# PCM2706_Bus_Powered_USB_DAC_2.net
KiCad netlist of a schematic drawn in Altium Designer
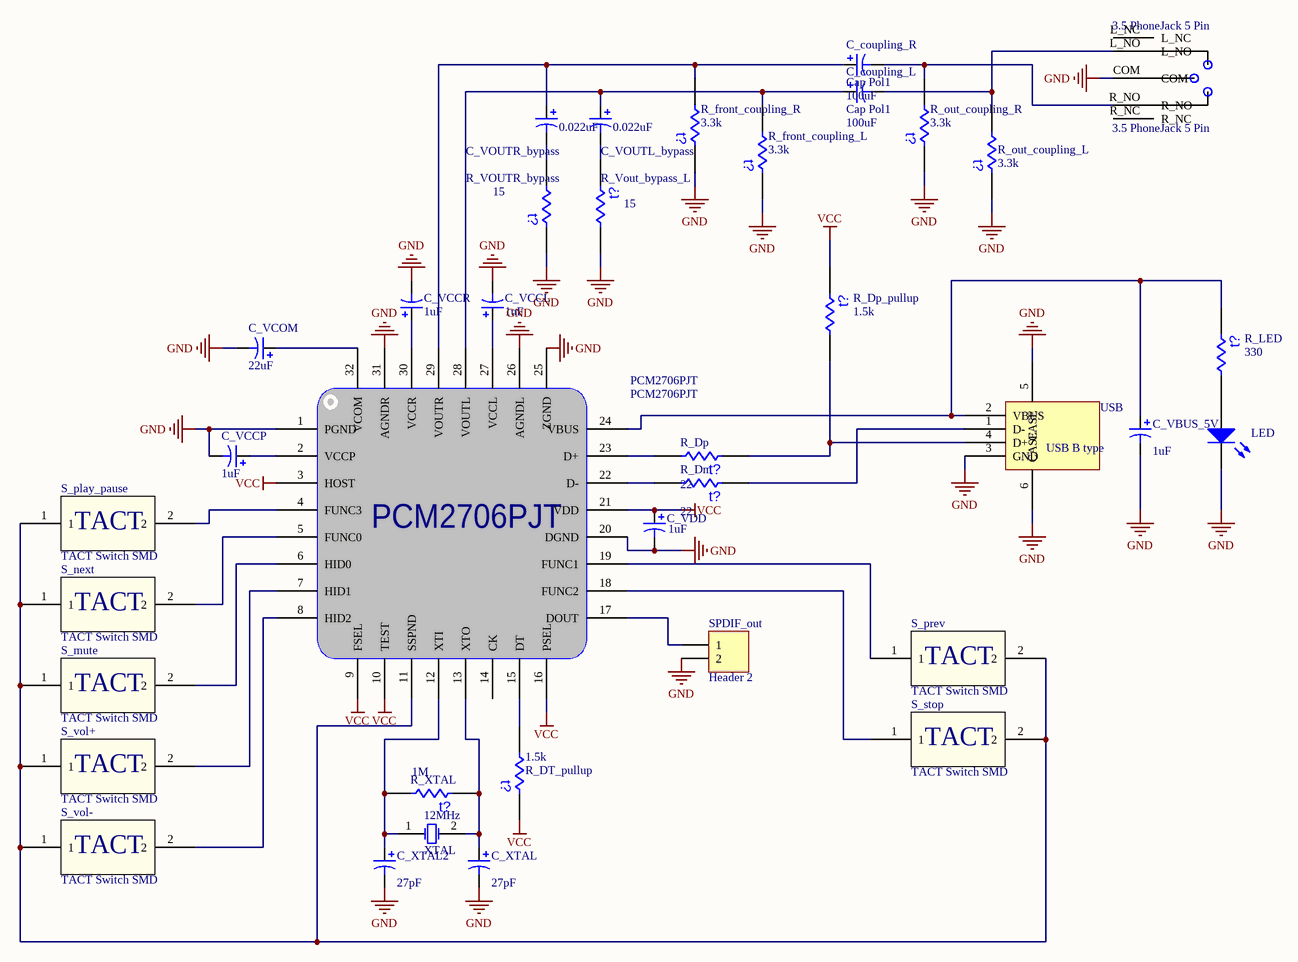
[diagram p0: PCM2706 Bus Powered USB DAC 2.SchDoc]

(export (version "E")
  (design (tool "Eeschema 10.0.6"))
  (components
    (comp (ref "1.5k")
      (value "R_DT_pullup")
      (footprint "6-0805_N")
      (description "Thermistor")
      (fields (field (name "PUBLISHER") "Altium Limited"))
      (libsource (lib "Miscellaneous Devices") (part "Res Thermal"))
    )
    (comp (ref "3.5 PhoneJack 5 Pin")
      (value "3.5 PhoneJack 5 Pin")
      (footprint "3.5 PhoneJack 5 Pin")
      (libsource (lib "misc") (part "3.5 PhoneJack 5 Pin"))
    )
    (comp (ref "12MHz")
      (value "XTAL")
      (footprint "12MHz Crystal OSC through hole")
      (description "Crystal Oscillator")
      (fields (field (name "PUBLISHER") "Altium Limited"))
      (libsource (lib "Miscellaneous Devices") (part "XTAL"))
    )
    (comp (ref "C_coupling_L")
      (value "Cap Pol1")
      (footprint "RB5-10.5_narrowed")
      (description "Polarized Capacitor (Radial)")
      (fields (field (name "ALTIUM_VALUE") "100uF") (field (name "PUBLISHER") "Altium Limited"))
      (libsource (lib "Miscellaneous Devices") (part "Cap Pol1"))
    )
    (comp (ref "C_coupling_R")
      (value "Cap Pol1")
      (footprint "RB5-10.5_narrowed")
      (description "Polarized Capacitor (Radial)")
      (fields (field (name "ALTIUM_VALUE") "100uF") (field (name "PUBLISHER") "Altium Limited"))
      (libsource (lib "Miscellaneous Devices") (part "Cap Pol1"))
    )
    (comp (ref "C_VBUS_5V")
      (value "1uF")
      (footprint "C0805")
      (description "Polarized Capacitor (Surface Mount)")
      (fields (field (name "PUBLISHER") "Altium Limited"))
      (libsource (lib "Miscellaneous Devices") (part "Cap Pol3"))
    )
    (comp (ref "C_VCCL")
      (value "1uF")
      (footprint "C0805")
      (description "Polarized Capacitor (Surface Mount)")
      (fields (field (name "PUBLISHER") "Altium Limited"))
      (libsource (lib "Miscellaneous Devices") (part "Cap Pol3"))
    )
    (comp (ref "C_VCCP")
      (value "1uF")
      (footprint "C0805")
      (description "Polarized Capacitor (Surface Mount)")
      (fields (field (name "PUBLISHER") "Altium Limited"))
      (libsource (lib "Miscellaneous Devices") (part "Cap Pol3"))
    )
    (comp (ref "C_VCCR")
      (value "1uF")
      (footprint "C0805")
      (description "Polarized Capacitor (Surface Mount)")
      (fields (field (name "PUBLISHER") "Altium Limited"))
      (libsource (lib "Miscellaneous Devices") (part "Cap Pol3"))
    )
    (comp (ref "C_VCOM")
      (value "22uF")
      (footprint "Tantalum 6032-28 case C kemet")
      (description "Polarized Capacitor (Surface Mount)")
      (fields (field (name "PUBLISHER") "Altium Limited"))
      (libsource (lib "Miscellaneous Devices") (part "Cap Pol3"))
    )
    (comp (ref "C_VDD")
      (value "1uF")
      (footprint "C0805")
      (description "Polarized Capacitor (Surface Mount)")
      (fields (field (name "PUBLISHER") "Altium Limited"))
      (libsource (lib "Miscellaneous Devices") (part "Cap Pol3"))
    )
    (comp (ref "C_VOUTL_bypass")
      (value "0.022uF")
      (footprint "C0805")
      (description "Polarized Capacitor (Surface Mount)")
      (fields (field (name "PUBLISHER") "Altium Limited"))
      (libsource (lib "Miscellaneous Devices") (part "Cap Pol3"))
    )
    (comp (ref "C_VOUTR_bypass")
      (value "0.022uF")
      (footprint "C0805")
      (description "Polarized Capacitor (Surface Mount)")
      (fields (field (name "PUBLISHER") "Altium Limited"))
      (libsource (lib "Miscellaneous Devices") (part "Cap Pol3"))
    )
    (comp (ref "C_XTAL")
      (value "27pF")
      (footprint "C0805")
      (description "Polarized Capacitor (Surface Mount)")
      (fields (field (name "PUBLISHER") "Altium Limited"))
      (libsource (lib "Miscellaneous Devices") (part "Cap Pol3"))
    )
    (comp (ref "C_XTAL2")
      (value "27pF")
      (footprint "C0805")
      (description "Polarized Capacitor (Surface Mount)")
      (fields (field (name "PUBLISHER") "Altium Limited"))
      (libsource (lib "Miscellaneous Devices") (part "Cap Pol3"))
    )
    (comp (ref "LED")
      (value "~")
      (footprint "6-0805_N_enlarge")
      (description "Typical RED, GREEN, YELLOW, AMBER GaAs LED")
      (fields (field (name "PUBLISHER") "Altium Limited"))
      (libsource (lib "Miscellaneous Devices") (part "LED2"))
    )
    (comp (ref "PCM2706PJT")
      (value "PCM2706PJT")
      (footprint "PCM2706PJT_2")
      (libsource (lib "misc") (part "PCM2706PJT"))
    )
    (comp (ref "R_Dm")
      (value "22")
      (footprint "6-0805_N")
      (description "Thermistor")
      (fields (field (name "PUBLISHER") "Altium Limited"))
      (libsource (lib "Miscellaneous Devices") (part "Res Thermal"))
    )
    (comp (ref "R_Dp")
      (value "22")
      (footprint "6-0805_N")
      (description "Thermistor")
      (fields (field (name "PUBLISHER") "Altium Limited"))
      (libsource (lib "Miscellaneous Devices") (part "Res Thermal"))
    )
    (comp (ref "R_Dp_pullup")
      (value "1.5k")
      (footprint "6-0805_N")
      (description "Thermistor")
      (fields (field (name "PUBLISHER") "Altium Limited"))
      (libsource (lib "Miscellaneous Devices") (part "Res Thermal"))
    )
    (comp (ref "R_front_coupling_L")
      (value "3.3k")
      (footprint "6-0805_N")
      (description "Thermistor")
      (fields (field (name "PUBLISHER") "Altium Limited"))
      (libsource (lib "Miscellaneous Devices") (part "Res Thermal"))
    )
    (comp (ref "R_front_coupling_R")
      (value "3.3k")
      (footprint "6-0805_N")
      (description "Thermistor")
      (fields (field (name "PUBLISHER") "Altium Limited"))
      (libsource (lib "Miscellaneous Devices") (part "Res Thermal"))
    )
    (comp (ref "R_LED")
      (value "330")
      (footprint "6-0805_N")
      (description "Thermistor")
      (fields (field (name "PUBLISHER") "Altium Limited"))
      (libsource (lib "Miscellaneous Devices") (part "Res Thermal"))
    )
    (comp (ref "R_out_coupling_L")
      (value "3.3k")
      (footprint "6-0805_N")
      (description "Thermistor")
      (fields (field (name "PUBLISHER") "Altium Limited"))
      (libsource (lib "Miscellaneous Devices") (part "Res Thermal"))
    )
    (comp (ref "R_out_coupling_R")
      (value "3.3k")
      (footprint "6-0805_N")
      (description "Thermistor")
      (fields (field (name "PUBLISHER") "Altium Limited"))
      (libsource (lib "Miscellaneous Devices") (part "Res Thermal"))
    )
    (comp (ref "R_VOUTR_bypass")
      (value "15")
      (footprint "6-0805_N")
      (description "Thermistor")
      (fields (field (name "PUBLISHER") "Altium Limited"))
      (libsource (lib "Miscellaneous Devices") (part "Res Thermal"))
    )
    (comp (ref "R_Vout_bypass_L")
      (value "15")
      (footprint "6-0805_N")
      (description "Thermistor")
      (fields (field (name "PUBLISHER") "Altium Limited"))
      (libsource (lib "Miscellaneous Devices") (part "Res Thermal"))
    )
    (comp (ref "R_XTAL")
      (value "1M")
      (footprint "6-0805_N")
      (description "Thermistor")
      (fields (field (name "PUBLISHER") "Altium Limited"))
      (libsource (lib "Miscellaneous Devices") (part "Res Thermal"))
    )
    (comp (ref "SPDIF_out")
      (value "Header 2")
      (footprint "HDR1X2")
      (description "Header, 2-Pin")
      (fields (field (name "PUBLISHER") "Altium Limited"))
      (libsource (lib "Miscellaneous Connectors") (part "Header 2"))
    )
    (comp (ref "S_mute")
      (value "TACT Switch SMD")
      (footprint "TACT Switch SMD")
      (libsource (lib "misc") (part "TACT Switch SMD"))
    )
    (comp (ref "S_next")
      (value "TACT Switch SMD")
      (footprint "TACT Switch SMD")
      (libsource (lib "misc") (part "TACT Switch SMD"))
    )
    (comp (ref "S_play_pause")
      (value "TACT Switch SMD")
      (footprint "TACT Switch SMD")
      (libsource (lib "misc") (part "TACT Switch SMD"))
    )
    (comp (ref "S_prev")
      (value "TACT Switch SMD")
      (footprint "TACT Switch SMD")
      (libsource (lib "misc") (part "TACT Switch SMD"))
    )
    (comp (ref "S_stop")
      (value "TACT Switch SMD")
      (footprint "TACT Switch SMD")
      (libsource (lib "misc") (part "TACT Switch SMD"))
    )
    (comp (ref "S_vol+")
      (value "TACT Switch SMD")
      (footprint "TACT Switch SMD")
      (libsource (lib "misc") (part "TACT Switch SMD"))
    )
    (comp (ref "S_vol-")
      (value "TACT Switch SMD")
      (footprint "TACT Switch SMD")
      (libsource (lib "misc") (part "TACT Switch SMD"))
    )
    (comp (ref "USB")
      (value "USB B type")
      (footprint "USB2.5-2H4D")
      (libsource (lib "misc") (part "USB B type"))
    )
  )
  (nets
    (net (code "1") (name "GND") (class "Default")
      (node (ref "3.5 PhoneJack 5 Pin") (pin "COM") (pinfunction "COM_COM") (pintype "passive"))
      (node (ref "C_VBUS_5V") (pin "2") (pinfunction "2_2") (pintype "passive"))
      (node (ref "C_VCCL") (pin "2") (pinfunction "2_2") (pintype "passive"))
      (node (ref "C_VCCP") (pin "2") (pinfunction "2_2") (pintype "passive"))
      (node (ref "C_VCCR") (pin "2") (pinfunction "2_2") (pintype "passive"))
      (node (ref "C_VCOM") (pin "2") (pinfunction "2_2") (pintype "passive"))
      (node (ref "C_VDD") (pin "2") (pinfunction "2_2") (pintype "passive"))
      (node (ref "C_XTAL") (pin "2") (pinfunction "2_2") (pintype "passive"))
      (node (ref "C_XTAL2") (pin "2") (pinfunction "2_2") (pintype "passive"))
      (node (ref "LED") (pin "2") (pinfunction "K_2") (pintype "passive"))
      (node (ref "PCM2706PJT") (pin "1") (pinfunction "PGND_1") (pintype "passive"))
      (node (ref "PCM2706PJT") (pin "20") (pinfunction "DGND_20") (pintype "passive"))
      (node (ref "PCM2706PJT") (pin "25") (pinfunction "ZGND_25") (pintype "passive"))
      (node (ref "PCM2706PJT") (pin "26") (pinfunction "AGNDL_26") (pintype "passive"))
      (node (ref "PCM2706PJT") (pin "31") (pinfunction "AGNDR_31") (pintype "passive"))
      (node (ref "R_VOUTR_bypass") (pin "1") (pinfunction "1_1") (pintype "passive"))
      (node (ref "R_Vout_bypass_L") (pin "2") (pinfunction "2_2") (pintype "passive"))
      (node (ref "R_front_coupling_L") (pin "1") (pinfunction "1_1") (pintype "passive"))
      (node (ref "R_front_coupling_R") (pin "1") (pinfunction "1_1") (pintype "passive"))
      (node (ref "R_out_coupling_L") (pin "1") (pinfunction "1_1") (pintype "passive"))
      (node (ref "R_out_coupling_R") (pin "1") (pinfunction "1_1") (pintype "passive"))
      (node (ref "SPDIF_out") (pin "1") (pinfunction "2_1") (pintype "passive"))
      (node (ref "USB") (pin "3") (pinfunction "GND_3") (pintype "passive"))
      (node (ref "USB") (pin "5") (pinfunction "CASE_5") (pintype "passive"))
      (node (ref "USB") (pin "6") (pinfunction "CASE_6") (pintype "passive"))
    )
    (net (code "2") (name "Net-(3.5 PhoneJack 5 Pin-PadL_NO)") (class "Default")
      (node (ref "3.5 PhoneJack 5 Pin") (pin "L_NO") (pinfunction "L_NO_L_NO") (pintype "passive"))
      (node (ref "C_coupling_L") (pin "2") (pinfunction "2_2") (pintype "passive"))
      (node (ref "R_out_coupling_L") (pin "2") (pinfunction "2_2") (pintype "passive"))
    )
    (net (code "3") (name "Net-(3.5 PhoneJack 5 Pin-PadR_NO)") (class "Default")
      (node (ref "3.5 PhoneJack 5 Pin") (pin "R_NO") (pinfunction "R_NO_R_NO") (pintype "passive"))
      (node (ref "C_coupling_R") (pin "2") (pinfunction "2_2") (pintype "passive"))
      (node (ref "R_out_coupling_R") (pin "2") (pinfunction "2_2") (pintype "passive"))
    )
    (net (code "4") (name "Net-(12MHz-OSC1)") (class "Default")
      (node (ref "12MHz") (pin "1") (pinfunction "OSC1_1") (pintype "passive"))
      (node (ref "C_XTAL2") (pin "1") (pinfunction "1_1") (pintype "passive"))
      (node (ref "PCM2706PJT") (pin "12") (pinfunction "XTI_12") (pintype "passive"))
      (node (ref "R_XTAL") (pin "2") (pinfunction "2_2") (pintype "passive"))
    )
    (net (code "5") (name "Net-(12MHz-OSC2)") (class "Default")
      (node (ref "12MHz") (pin "2") (pinfunction "OSC2_2") (pintype "passive"))
      (node (ref "C_XTAL") (pin "1") (pinfunction "1_1") (pintype "passive"))
      (node (ref "PCM2706PJT") (pin "13") (pinfunction "XTO_13") (pintype "passive"))
      (node (ref "R_XTAL") (pin "1") (pinfunction "1_1") (pintype "passive"))
    )
    (net (code "6") (name "Net-(C_VOUTL_bypass-Pad2)") (class "Default")
      (node (ref "C_VOUTL_bypass") (pin "2") (pinfunction "2_2") (pintype "passive"))
      (node (ref "R_Vout_bypass_L") (pin "1") (pinfunction "1_1") (pintype "passive"))
    )
    (net (code "7") (name "Net-(C_VOUTR_bypass-Pad2)") (class "Default")
      (node (ref "C_VOUTR_bypass") (pin "2") (pinfunction "2_2") (pintype "passive"))
      (node (ref "R_VOUTR_bypass") (pin "2") (pinfunction "2_2") (pintype "passive"))
    )
    (net (code "8") (name "Net-(LED-A)") (class "Default")
      (node (ref "LED") (pin "1") (pinfunction "A_1") (pintype "passive"))
      (node (ref "R_LED") (pin "2") (pinfunction "2_2") (pintype "passive"))
    )
    (net (code "9") (name "Net-(PCM2706PJT-D+)") (class "Default")
      (node (ref "PCM2706PJT") (pin "23") (pinfunction "D+_23") (pintype "passive"))
      (node (ref "R_Dp") (pin "2") (pinfunction "2_2") (pintype "passive"))
    )
    (net (code "10") (name "Net-(PCM2706PJT-D-)") (class "Default")
      (node (ref "PCM2706PJT") (pin "22") (pinfunction "D-_22") (pintype "passive"))
      (node (ref "R_Dm") (pin "2") (pinfunction "2_2") (pintype "passive"))
    )
    (net (code "11") (name "Net-(PCM2706PJT-DOUT)") (class "Default")
      (node (ref "PCM2706PJT") (pin "17") (pinfunction "DOUT_17") (pintype "passive"))
      (node (ref "SPDIF_out") (pin "2") (pinfunction "1_2") (pintype "passive"))
    )
    (net (code "12") (name "Net-(PCM2706PJT-DT)") (class "Default")
      (node (ref "1.5k") (pin "2") (pinfunction "2_2") (pintype "passive"))
      (node (ref "PCM2706PJT") (pin "15") (pinfunction "DT_15") (pintype "passive"))
    )
    (net (code "13") (name "Net-(PCM2706PJT-FUNC0)") (class "Default")
      (node (ref "PCM2706PJT") (pin "5") (pinfunction "FUNC0_5") (pintype "passive"))
      (node (ref "S_next") (pin "2") (pinfunction "2_2") (pintype "passive"))
    )
    (net (code "14") (name "Net-(PCM2706PJT-FUNC1)") (class "Default")
      (node (ref "PCM2706PJT") (pin "19") (pinfunction "FUNC1_19") (pintype "passive"))
      (node (ref "S_prev") (pin "1") (pinfunction "1_1") (pintype "passive"))
    )
    (net (code "15") (name "Net-(PCM2706PJT-FUNC2)") (class "Default")
      (node (ref "PCM2706PJT") (pin "18") (pinfunction "FUNC2_18") (pintype "passive"))
      (node (ref "S_stop") (pin "1") (pinfunction "1_1") (pintype "passive"))
    )
    (net (code "16") (name "Net-(PCM2706PJT-FUNC3)") (class "Default")
      (node (ref "PCM2706PJT") (pin "4") (pinfunction "FUNC3_4") (pintype "passive"))
      (node (ref "S_play_pause") (pin "2") (pinfunction "2_2") (pintype "passive"))
    )
    (net (code "17") (name "Net-(PCM2706PJT-HID0)") (class "Default")
      (node (ref "PCM2706PJT") (pin "6") (pinfunction "HID0_6") (pintype "passive"))
      (node (ref "S_mute") (pin "2") (pinfunction "2_2") (pintype "passive"))
    )
    (net (code "18") (name "Net-(PCM2706PJT-HID1)") (class "Default")
      (node (ref "PCM2706PJT") (pin "7") (pinfunction "HID1_7") (pintype "passive"))
      (node (ref "S_vol+") (pin "2") (pinfunction "2_2") (pintype "passive"))
    )
    (net (code "19") (name "Net-(PCM2706PJT-HID2)") (class "Default")
      (node (ref "PCM2706PJT") (pin "8") (pinfunction "HID2_8") (pintype "passive"))
      (node (ref "S_vol-") (pin "2") (pinfunction "2_2") (pintype "passive"))
    )
    (net (code "20") (name "Net-(PCM2706PJT-SSPND)") (class "Default")
      (node (ref "PCM2706PJT") (pin "11") (pinfunction "SSPND_11") (pintype "passive"))
      (node (ref "S_mute") (pin "1") (pinfunction "1_1") (pintype "passive"))
      (node (ref "S_next") (pin "1") (pinfunction "1_1") (pintype "passive"))
      (node (ref "S_play_pause") (pin "1") (pinfunction "1_1") (pintype "passive"))
      (node (ref "S_prev") (pin "2") (pinfunction "2_2") (pintype "passive"))
      (node (ref "S_stop") (pin "2") (pinfunction "2_2") (pintype "passive"))
      (node (ref "S_vol+") (pin "1") (pinfunction "1_1") (pintype "passive"))
      (node (ref "S_vol-") (pin "1") (pinfunction "1_1") (pintype "passive"))
    )
    (net (code "21") (name "Net-(PCM2706PJT-VBUS)") (class "Default")
      (node (ref "C_VBUS_5V") (pin "1") (pinfunction "1_1") (pintype "passive"))
      (node (ref "PCM2706PJT") (pin "24") (pinfunction "VBUS_24") (pintype "passive"))
      (node (ref "R_LED") (pin "1") (pinfunction "1_1") (pintype "passive"))
      (node (ref "USB") (pin "2") (pinfunction "VBUS_2") (pintype "passive"))
    )
    (net (code "22") (name "Net-(PCM2706PJT-VCCL)") (class "Default")
      (node (ref "C_VCCL") (pin "1") (pinfunction "1_1") (pintype "passive"))
      (node (ref "PCM2706PJT") (pin "27") (pinfunction "VCCL_27") (pintype "passive"))
    )
    (net (code "23") (name "Net-(PCM2706PJT-VCCP)") (class "Default")
      (node (ref "C_VCCP") (pin "1") (pinfunction "1_1") (pintype "passive"))
      (node (ref "PCM2706PJT") (pin "2") (pinfunction "VCCP_2") (pintype "passive"))
    )
    (net (code "24") (name "Net-(PCM2706PJT-VCCR)") (class "Default")
      (node (ref "C_VCCR") (pin "1") (pinfunction "1_1") (pintype "passive"))
      (node (ref "PCM2706PJT") (pin "30") (pinfunction "VCCR_30") (pintype "passive"))
    )
    (net (code "25") (name "Net-(PCM2706PJT-VCOM)") (class "Default")
      (node (ref "C_VCOM") (pin "1") (pinfunction "1_1") (pintype "passive"))
      (node (ref "PCM2706PJT") (pin "32") (pinfunction "VCOM_32") (pintype "passive"))
    )
    (net (code "26") (name "Net-(PCM2706PJT-VOUTL)") (class "Default")
      (node (ref "C_VOUTL_bypass") (pin "1") (pinfunction "1_1") (pintype "passive"))
      (node (ref "C_coupling_L") (pin "1") (pinfunction "1_1") (pintype "passive"))
      (node (ref "PCM2706PJT") (pin "28") (pinfunction "VOUTL_28") (pintype "passive"))
      (node (ref "R_front_coupling_L") (pin "2") (pinfunction "2_2") (pintype "passive"))
    )
    (net (code "27") (name "Net-(PCM2706PJT-VOUTR)") (class "Default")
      (node (ref "C_VOUTR_bypass") (pin "1") (pinfunction "1_1") (pintype "passive"))
      (node (ref "C_coupling_R") (pin "1") (pinfunction "1_1") (pintype "passive"))
      (node (ref "PCM2706PJT") (pin "29") (pinfunction "VOUTR_29") (pintype "passive"))
      (node (ref "R_front_coupling_R") (pin "2") (pinfunction "2_2") (pintype "passive"))
    )
    (net (code "28") (name "Net-(USB-D+)") (class "Default")
      (node (ref "R_Dp") (pin "1") (pinfunction "1_1") (pintype "passive"))
      (node (ref "R_Dp_pullup") (pin "2") (pinfunction "2_2") (pintype "passive"))
      (node (ref "USB") (pin "4") (pinfunction "D+_4") (pintype "passive"))
    )
    (net (code "29") (name "Net-(USB-D-)") (class "Default")
      (node (ref "R_Dm") (pin "1") (pinfunction "1_1") (pintype "passive"))
      (node (ref "USB") (pin "1") (pinfunction "D-_1") (pintype "passive"))
    )
    (net (code "30") (name "VCC") (class "Default")
      (node (ref "1.5k") (pin "1") (pinfunction "1_1") (pintype "passive"))
      (node (ref "C_VDD") (pin "1") (pinfunction "1_1") (pintype "passive"))
      (node (ref "PCM2706PJT") (pin "10") (pinfunction "TEST_10") (pintype "passive"))
      (node (ref "PCM2706PJT") (pin "16") (pinfunction "PSEL_16") (pintype "passive"))
      (node (ref "PCM2706PJT") (pin "21") (pinfunction "VDD_21") (pintype "passive"))
      (node (ref "PCM2706PJT") (pin "3") (pinfunction "HOST_3") (pintype "passive"))
      (node (ref "PCM2706PJT") (pin "9") (pinfunction "FSEL_9") (pintype "passive"))
      (node (ref "R_Dp_pullup") (pin "1") (pinfunction "1_1") (pintype "passive"))
    )
    (net (code "31") (name "unconnected-(3.5 PhoneJack 5 Pin-PadL_NC)") (class "Default")
      (node (ref "3.5 PhoneJack 5 Pin") (pin "L_NC") (pinfunction "L_NC_L_NC") (pintype "passive"))
    )
    (net (code "32") (name "unconnected-(3.5 PhoneJack 5 Pin-PadR_NC)") (class "Default")
      (node (ref "3.5 PhoneJack 5 Pin") (pin "R_NC") (pinfunction "R_NC_R_NC") (pintype "passive"))
    )
    (net (code "33") (name "unconnected-(PCM2706PJT-CK-Pad14)") (class "Default")
      (node (ref "PCM2706PJT") (pin "14") (pinfunction "CK_14") (pintype "passive"))
    )
  )
)
